# Level_Shifting_Connectors.net
KiCad netlist of a schematic drawn in Altium Designer
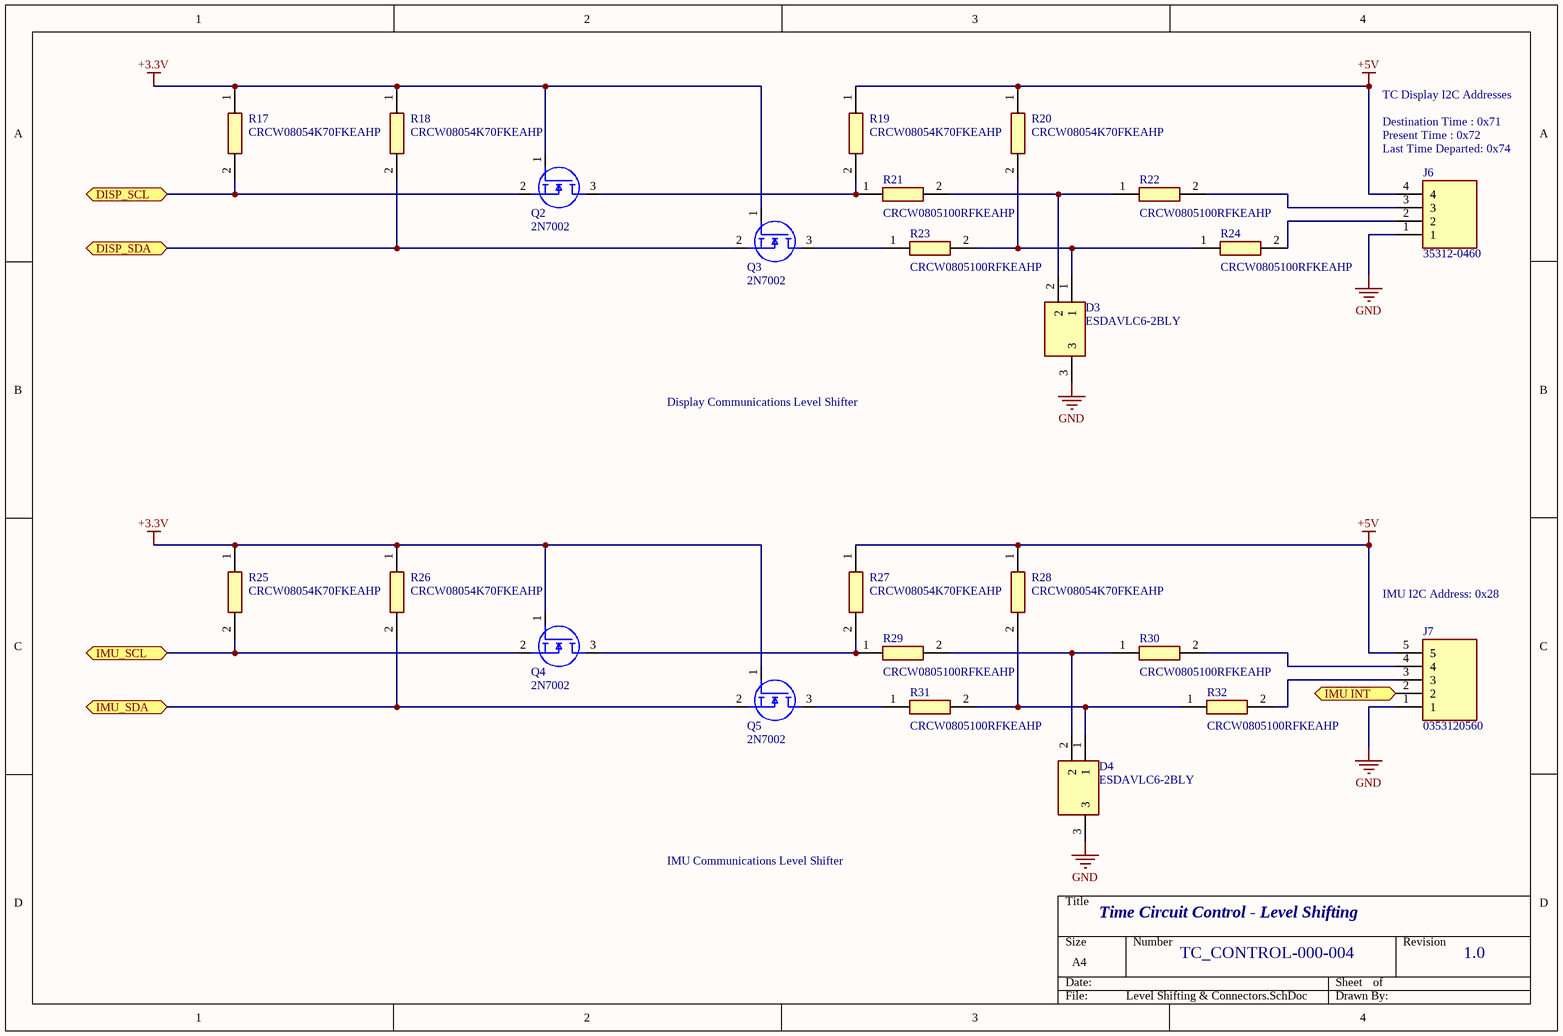
[diagram p0: Level Shifting & Connectors.SchDoc]

(export (version "E")
  (design (tool "Eeschema 10.0.6"))
  (components
    (comp (ref "D3")
      (value "ESDAVLC6-2BLY")
      (footprint "SamacSys:SOT95P255X150-3N")
      (description "TVS Diode (Bi-directional)")
      (fields (field (name "MOUSER PART NUMBER") "511-ESDAVLC6-2BLY"))
      (libsource (lib "SamacSys") (part "ESDAVLC6-2BLY"))
    )
    (comp (ref "D4")
      (value "ESDAVLC6-2BLY")
      (footprint "SamacSys:SOT95P255X150-3N")
      (description "TVS Diode (Bi-directional)")
      (fields (field (name "MOUSER PART NUMBER") "511-ESDAVLC6-2BLY"))
      (libsource (lib "SamacSys") (part "ESDAVLC6-2BLY"))
    )
    (comp (ref "J6")
      (value "35312-0460")
      (footprint "SamacSys:SHDR4W64P0X250_1X4_1246X650X700P")
      (description "Connector")
      (fields (field (name "MOUSER PART NUMBER") "538-35312-0460"))
      (libsource (lib "SamacSys") (part "35312-0460"))
    )
    (comp (ref "J7")
      (value "0353120560")
      (footprint "SamacSys:0353120560")
      (description "Connector")
      (libsource (lib "SamacSys") (part "0353120560"))
    )
    (comp (ref "Q2")
      (value "2N7002")
      (footprint "SamacSys:SOT96P240X120-3N")
      (description "MOSFET (N-Channel)")
      (fields (field (name "MOUSER PART NUMBER") "781-2N7002"))
      (libsource (lib "SamacSys") (part "2N7002"))
    )
    (comp (ref "Q3")
      (value "2N7002")
      (footprint "SamacSys:SOT96P240X120-3N")
      (description "MOSFET (N-Channel)")
      (fields (field (name "MOUSER PART NUMBER") "781-2N7002"))
      (libsource (lib "SamacSys") (part "2N7002"))
    )
    (comp (ref "Q4")
      (value "2N7002")
      (footprint "SamacSys:SOT96P240X120-3N")
      (description "MOSFET (N-Channel)")
      (fields (field (name "MOUSER PART NUMBER") "781-2N7002"))
      (libsource (lib "SamacSys") (part "2N7002"))
    )
    (comp (ref "Q5")
      (value "2N7002")
      (footprint "SamacSys:SOT96P240X120-3N")
      (description "MOSFET (N-Channel)")
      (fields (field (name "MOUSER PART NUMBER") "781-2N7002"))
      (libsource (lib "SamacSys") (part "2N7002"))
    )
    (comp (ref "R17")
      (value "CRCW08054K70FKEAHP")
      (footprint "SamacSys:RESC2012X50N")
      (description "Resistor")
      (fields (field (name "MOUSER PART NUMBER") "71-CRCW08054K70FKEAH"))
      (libsource (lib "SamacSys") (part "CRCW08054K70FKEAHP"))
    )
    (comp (ref "R18")
      (value "CRCW08054K70FKEAHP")
      (footprint "SamacSys:RESC2012X50N")
      (description "Resistor")
      (fields (field (name "MOUSER PART NUMBER") "71-CRCW08054K70FKEAH"))
      (libsource (lib "SamacSys") (part "CRCW08054K70FKEAHP"))
    )
    (comp (ref "R19")
      (value "CRCW08054K70FKEAHP")
      (footprint "SamacSys:RESC2012X50N")
      (description "Resistor")
      (fields (field (name "MOUSER PART NUMBER") "71-CRCW08054K70FKEAH"))
      (libsource (lib "SamacSys") (part "CRCW08054K70FKEAHP"))
    )
    (comp (ref "R20")
      (value "CRCW08054K70FKEAHP")
      (footprint "SamacSys:RESC2012X50N")
      (description "Resistor")
      (fields (field (name "MOUSER PART NUMBER") "71-CRCW08054K70FKEAH"))
      (libsource (lib "SamacSys") (part "CRCW08054K70FKEAHP"))
    )
    (comp (ref "R21")
      (value "CRCW0805100RFKEAHP")
      (footprint "SamacSys:RESC2012X50N")
      (description "Resistor")
      (fields (field (name "MOUSER PART NUMBER") "71-CRCW0805100RFKEAH"))
      (libsource (lib "SamacSys") (part "CRCW0805100RFKEAHP"))
    )
    (comp (ref "R22")
      (value "CRCW0805100RFKEAHP")
      (footprint "SamacSys:RESC2012X50N")
      (description "Resistor")
      (fields (field (name "MOUSER PART NUMBER") "71-CRCW0805100RFKEAH"))
      (libsource (lib "SamacSys") (part "CRCW0805100RFKEAHP"))
    )
    (comp (ref "R23")
      (value "CRCW0805100RFKEAHP")
      (footprint "SamacSys:RESC2012X50N")
      (description "Resistor")
      (fields (field (name "MOUSER PART NUMBER") "71-CRCW0805100RFKEAH"))
      (libsource (lib "SamacSys") (part "CRCW0805100RFKEAHP"))
    )
    (comp (ref "R24")
      (value "CRCW0805100RFKEAHP")
      (footprint "SamacSys:RESC2012X50N")
      (description "Resistor")
      (fields (field (name "MOUSER PART NUMBER") "71-CRCW0805100RFKEAH"))
      (libsource (lib "SamacSys") (part "CRCW0805100RFKEAHP"))
    )
    (comp (ref "R25")
      (value "CRCW08054K70FKEAHP")
      (footprint "SamacSys:RESC2012X50N")
      (description "Resistor")
      (fields (field (name "MOUSER PART NUMBER") "71-CRCW08054K70FKEAH"))
      (libsource (lib "SamacSys") (part "CRCW08054K70FKEAHP"))
    )
    (comp (ref "R26")
      (value "CRCW08054K70FKEAHP")
      (footprint "SamacSys:RESC2012X50N")
      (description "Resistor")
      (fields (field (name "MOUSER PART NUMBER") "71-CRCW08054K70FKEAH"))
      (libsource (lib "SamacSys") (part "CRCW08054K70FKEAHP"))
    )
    (comp (ref "R27")
      (value "CRCW08054K70FKEAHP")
      (footprint "SamacSys:RESC2012X50N")
      (description "Resistor")
      (fields (field (name "MOUSER PART NUMBER") "71-CRCW08054K70FKEAH"))
      (libsource (lib "SamacSys") (part "CRCW08054K70FKEAHP"))
    )
    (comp (ref "R28")
      (value "CRCW08054K70FKEAHP")
      (footprint "SamacSys:RESC2012X50N")
      (description "Resistor")
      (fields (field (name "MOUSER PART NUMBER") "71-CRCW08054K70FKEAH"))
      (libsource (lib "SamacSys") (part "CRCW08054K70FKEAHP"))
    )
    (comp (ref "R29")
      (value "CRCW0805100RFKEAHP")
      (footprint "SamacSys:RESC2012X50N")
      (description "Resistor")
      (fields (field (name "MOUSER PART NUMBER") "71-CRCW0805100RFKEAH"))
      (libsource (lib "SamacSys") (part "CRCW0805100RFKEAHP"))
    )
    (comp (ref "R30")
      (value "CRCW0805100RFKEAHP")
      (footprint "SamacSys:RESC2012X50N")
      (description "Resistor")
      (fields (field (name "MOUSER PART NUMBER") "71-CRCW0805100RFKEAH"))
      (libsource (lib "SamacSys") (part "CRCW0805100RFKEAHP"))
    )
    (comp (ref "R31")
      (value "CRCW0805100RFKEAHP")
      (footprint "SamacSys:RESC2012X50N")
      (description "Resistor")
      (fields (field (name "MOUSER PART NUMBER") "71-CRCW0805100RFKEAH"))
      (libsource (lib "SamacSys") (part "CRCW0805100RFKEAHP"))
    )
    (comp (ref "R32")
      (value "CRCW0805100RFKEAHP")
      (footprint "SamacSys:RESC2012X50N")
      (description "Resistor")
      (fields (field (name "MOUSER PART NUMBER") "71-CRCW0805100RFKEAH"))
      (libsource (lib "SamacSys") (part "CRCW0805100RFKEAHP"))
    )
  )
  (nets
    (net (code "1") (name "+3.3V") (class "Default")
      (node (ref "Q2") (pin "1") (pinfunction "G_1") (pintype "passive"))
      (node (ref "Q3") (pin "1") (pinfunction "G_1") (pintype "passive"))
      (node (ref "Q4") (pin "1") (pinfunction "G_1") (pintype "passive"))
      (node (ref "Q5") (pin "1") (pinfunction "G_1") (pintype "passive"))
      (node (ref "R17") (pin "1") (pinfunction "1_1") (pintype "passive"))
      (node (ref "R18") (pin "1") (pinfunction "1_1") (pintype "passive"))
      (node (ref "R25") (pin "1") (pinfunction "1_1") (pintype "passive"))
      (node (ref "R26") (pin "1") (pinfunction "1_1") (pintype "passive"))
    )
    (net (code "2") (name "+5V") (class "Default")
      (node (ref "J6") (pin "4") (pinfunction "4_4") (pintype "passive"))
      (node (ref "J7") (pin "5") (pinfunction "5_5") (pintype "passive"))
      (node (ref "R19") (pin "1") (pinfunction "1_1") (pintype "passive"))
      (node (ref "R20") (pin "1") (pinfunction "1_1") (pintype "passive"))
      (node (ref "R27") (pin "1") (pinfunction "1_1") (pintype "passive"))
      (node (ref "R28") (pin "1") (pinfunction "1_1") (pintype "passive"))
    )
    (net (code "3") (name "/DISP_SCL") (class "Default")
      (node (ref "Q2") (pin "2") (pinfunction "S_2") (pintype "passive"))
      (node (ref "R17") (pin "2") (pinfunction "2_2") (pintype "passive"))
    )
    (net (code "4") (name "/DISP_SDA") (class "Default")
      (node (ref "Q3") (pin "2") (pinfunction "S_2") (pintype "passive"))
      (node (ref "R18") (pin "2") (pinfunction "2_2") (pintype "passive"))
    )
    (net (code "5") (name "/IMU INT") (class "Default")
      (node (ref "J7") (pin "2") (pinfunction "2_2") (pintype "passive"))
    )
    (net (code "6") (name "/IMU_SCL") (class "Default")
      (node (ref "Q4") (pin "2") (pinfunction "S_2") (pintype "passive"))
      (node (ref "R25") (pin "2") (pinfunction "2_2") (pintype "passive"))
    )
    (net (code "7") (name "/IMU_SDA") (class "Default")
      (node (ref "Q5") (pin "2") (pinfunction "S_2") (pintype "passive"))
      (node (ref "R26") (pin "2") (pinfunction "2_2") (pintype "passive"))
    )
    (net (code "8") (name "GND") (class "Default")
      (node (ref "D3") (pin "3") (pinfunction "3_3") (pintype "passive"))
      (node (ref "D4") (pin "3") (pinfunction "3_3") (pintype "passive"))
      (node (ref "J6") (pin "1") (pinfunction "1_1") (pintype "passive"))
      (node (ref "J7") (pin "1") (pinfunction "1_1") (pintype "passive"))
    )
    (net (code "9") (name "Net-(D3-Pad1)") (class "Default")
      (node (ref "D3") (pin "1") (pinfunction "1_1") (pintype "passive"))
      (node (ref "R20") (pin "2") (pinfunction "2_2") (pintype "passive"))
      (node (ref "R23") (pin "2") (pinfunction "2_2") (pintype "passive"))
      (node (ref "R24") (pin "1") (pinfunction "1_1") (pintype "passive"))
    )
    (net (code "10") (name "Net-(D3-Pad2)") (class "Default")
      (node (ref "D3") (pin "2") (pinfunction "2_2") (pintype "passive"))
      (node (ref "R21") (pin "2") (pinfunction "2_2") (pintype "passive"))
      (node (ref "R22") (pin "1") (pinfunction "1_1") (pintype "passive"))
    )
    (net (code "11") (name "Net-(D4-Pad1)") (class "Default")
      (node (ref "D4") (pin "1") (pinfunction "1_1") (pintype "passive"))
      (node (ref "R28") (pin "2") (pinfunction "2_2") (pintype "passive"))
      (node (ref "R31") (pin "2") (pinfunction "2_2") (pintype "passive"))
      (node (ref "R32") (pin "1") (pinfunction "1_1") (pintype "passive"))
    )
    (net (code "12") (name "Net-(D4-Pad2)") (class "Default")
      (node (ref "D4") (pin "2") (pinfunction "2_2") (pintype "passive"))
      (node (ref "R29") (pin "2") (pinfunction "2_2") (pintype "passive"))
      (node (ref "R30") (pin "1") (pinfunction "1_1") (pintype "passive"))
    )
    (net (code "13") (name "Net-(J6-Pad2)") (class "Default")
      (node (ref "J6") (pin "2") (pinfunction "2_2") (pintype "passive"))
      (node (ref "R24") (pin "2") (pinfunction "2_2") (pintype "passive"))
    )
    (net (code "14") (name "Net-(J6-Pad3)") (class "Default")
      (node (ref "J6") (pin "3") (pinfunction "3_3") (pintype "passive"))
      (node (ref "R22") (pin "2") (pinfunction "2_2") (pintype "passive"))
    )
    (net (code "15") (name "Net-(J7-Pad3)") (class "Default")
      (node (ref "J7") (pin "3") (pinfunction "3_3") (pintype "passive"))
      (node (ref "R32") (pin "2") (pinfunction "2_2") (pintype "passive"))
    )
    (net (code "16") (name "Net-(J7-Pad4)") (class "Default")
      (node (ref "J7") (pin "4") (pinfunction "4_4") (pintype "passive"))
      (node (ref "R30") (pin "2") (pinfunction "2_2") (pintype "passive"))
    )
    (net (code "17") (name "Net-(Q2-D)") (class "Default")
      (node (ref "Q2") (pin "3") (pinfunction "D_3") (pintype "passive"))
      (node (ref "R19") (pin "2") (pinfunction "2_2") (pintype "passive"))
      (node (ref "R21") (pin "1") (pinfunction "1_1") (pintype "passive"))
    )
    (net (code "18") (name "Net-(Q3-D)") (class "Default")
      (node (ref "Q3") (pin "3") (pinfunction "D_3") (pintype "passive"))
      (node (ref "R23") (pin "1") (pinfunction "1_1") (pintype "passive"))
    )
    (net (code "19") (name "Net-(Q4-D)") (class "Default")
      (node (ref "Q4") (pin "3") (pinfunction "D_3") (pintype "passive"))
      (node (ref "R27") (pin "2") (pinfunction "2_2") (pintype "passive"))
      (node (ref "R29") (pin "1") (pinfunction "1_1") (pintype "passive"))
    )
    (net (code "20") (name "Net-(Q5-D)") (class "Default")
      (node (ref "Q5") (pin "3") (pinfunction "D_3") (pintype "passive"))
      (node (ref "R31") (pin "1") (pinfunction "1_1") (pintype "passive"))
    )
  )
)
